# bits.net
KiCad netlist of a schematic drawn in EAGLE
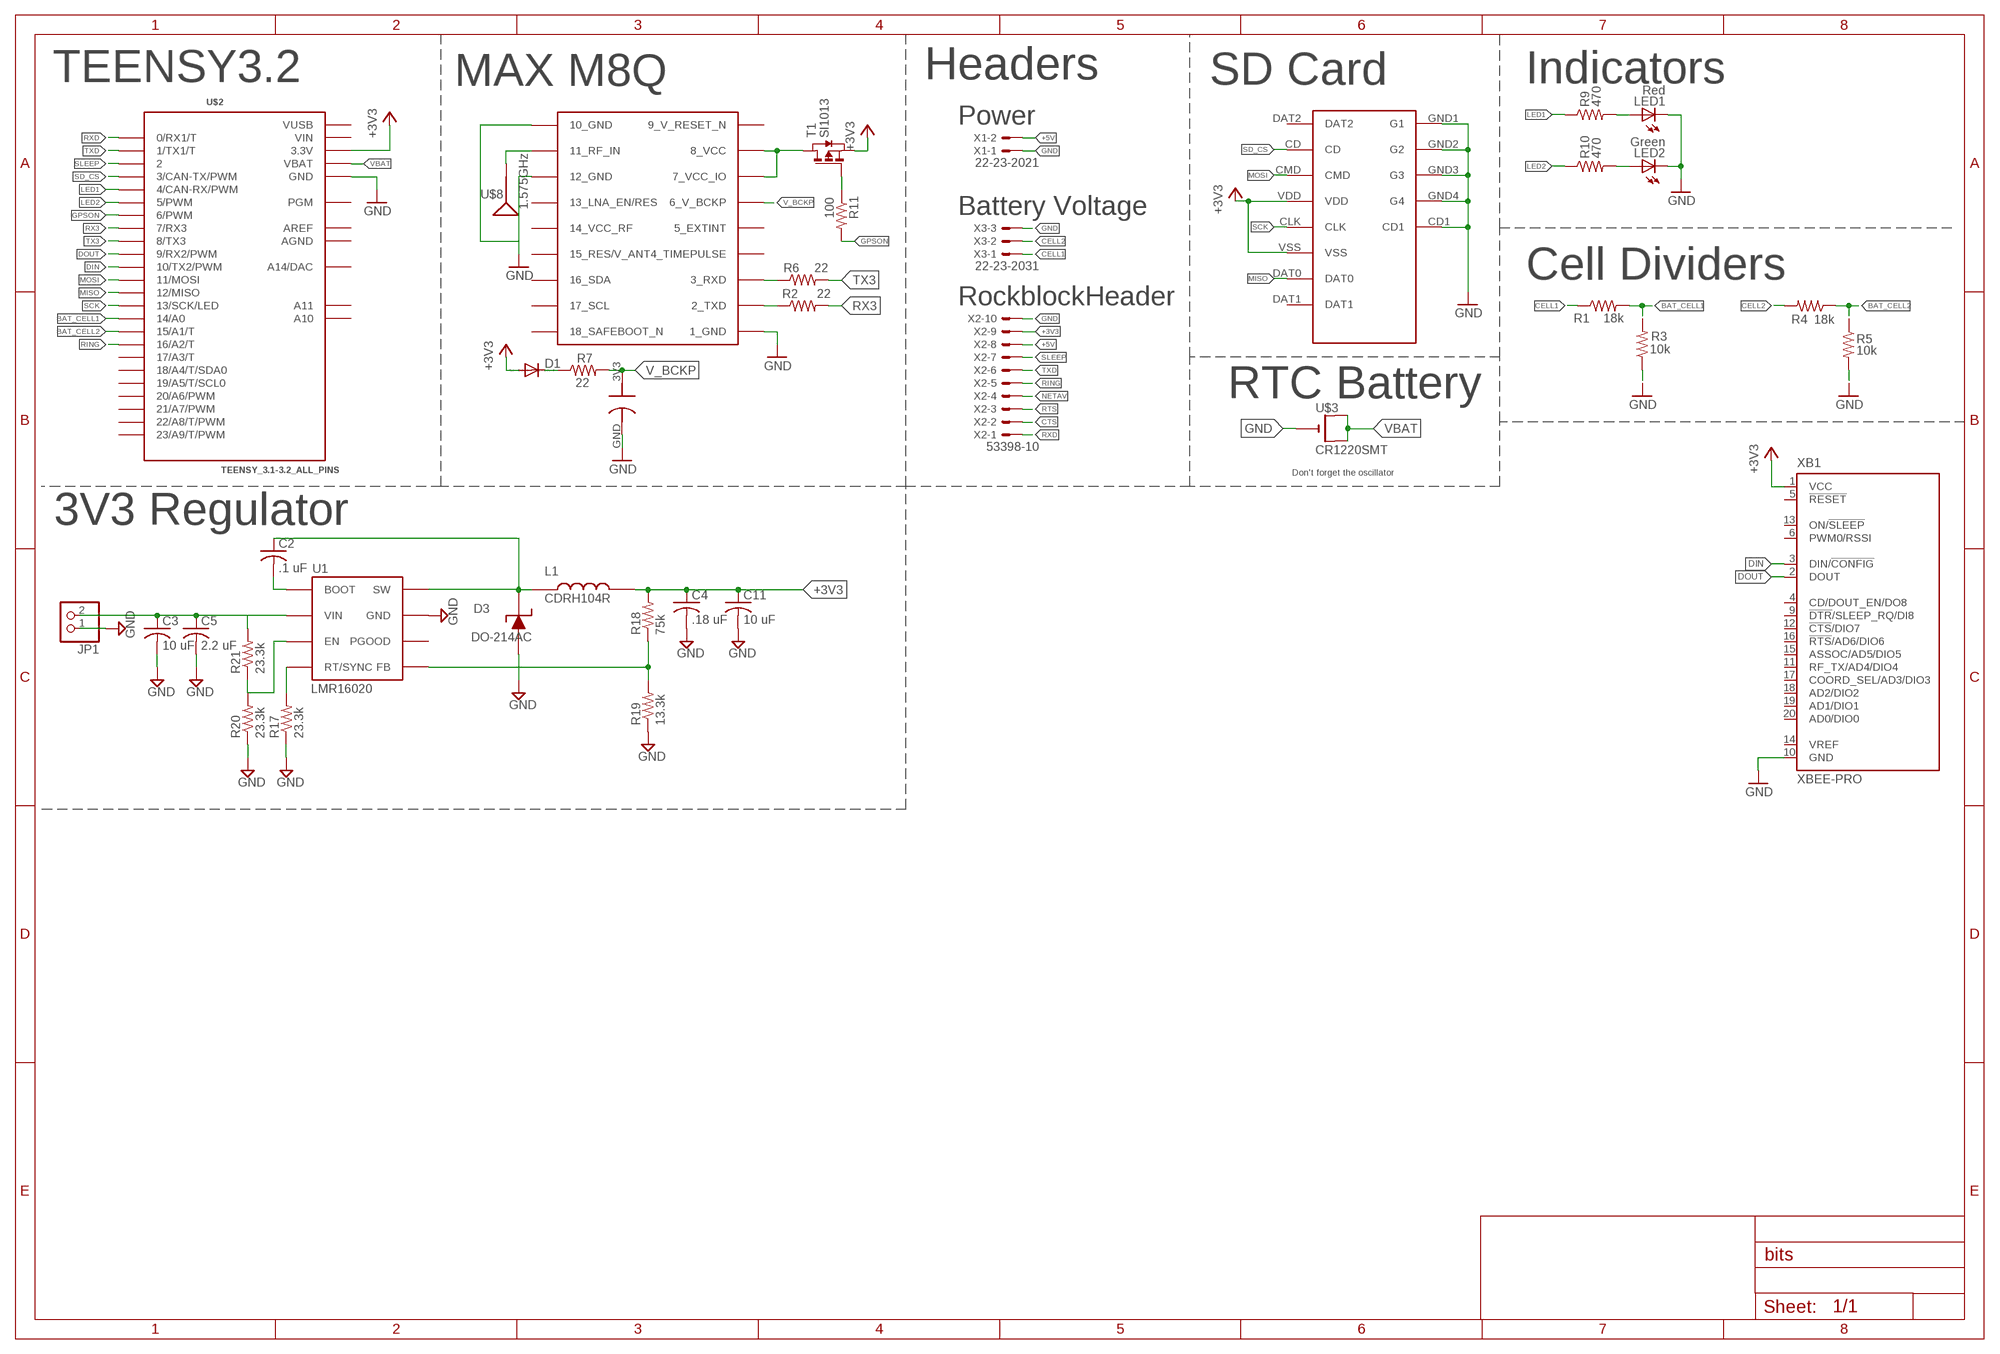
[diagram p0: schematic, sheet 1]

(export (version "E")
  (design (tool "Eeschema 10.0.6"))
  (components
    (comp (ref "C1")
      (value "DCK-3R3E204T614-E")
      (footprint "eagle-import:ELNASUPERCAP")
      (libsource (lib "eagle-import") (part "DCK-3R3E204T614-E"))
    )
    (comp (ref "C2")
      (value ".1 uF")
      (footprint "eagle-import:C0603")
      (libsource (lib "eagle-import") (part "C-USC0603"))
    )
    (comp (ref "C3")
      (value "10 uF")
      (footprint "eagle-import:C1210")
      (libsource (lib "eagle-import") (part "C-USC1210"))
    )
    (comp (ref "C4")
      (value ".18 uF")
      (footprint "eagle-import:C0603")
      (libsource (lib "eagle-import") (part "C-USC0603"))
    )
    (comp (ref "C5")
      (value "2.2 uF")
      (footprint "eagle-import:C1210")
      (libsource (lib "eagle-import") (part "C-USC1210"))
    )
    (comp (ref "C11")
      (value "10 uF")
      (footprint "eagle-import:C0603")
      (libsource (lib "eagle-import") (part "C-USC0603"))
    )
    (comp (ref "D1")
      (value "DIODE-SOD523")
      (footprint "eagle-import:SOD523")
      (libsource (lib "eagle-import") (part "DIODE-SOD523"))
    )
    (comp (ref "D3")
      (value "DO-214AC")
      (footprint "eagle-import:DO-214AC")
      (libsource (lib "eagle-import") (part "DO-214AC"))
    )
    (comp (ref "JP1")
      (value "PINHD-1X2")
      (footprint "eagle-import:1X02")
      (libsource (lib "eagle-import") (part "PINHD-1X2"))
    )
    (comp (ref "L1")
      (value "CDRH104R")
      (footprint "eagle-import:CDRH104R")
      (libsource (lib "eagle-import") (part "CDRH104R"))
    )
    (comp (ref "LED1")
      (value "Red")
      (footprint "eagle-import:CHIP-LED0603")
      (libsource (lib "eagle-import") (part "LEDCHIP-LED0603"))
    )
    (comp (ref "LED2")
      (value "Green")
      (footprint "eagle-import:CHIP-LED0603")
      (libsource (lib "eagle-import") (part "LEDCHIP-LED0603"))
    )
    (comp (ref "R1")
      (value "18k")
      (footprint "eagle-import:R0603")
      (libsource (lib "eagle-import") (part "resistor_R-US_R0603"))
    )
    (comp (ref "R2")
      (value "22")
      (footprint "eagle-import:R0603")
      (libsource (lib "eagle-import") (part "R-US_R0603"))
    )
    (comp (ref "R3")
      (value "10k")
      (footprint "eagle-import:R0603")
      (libsource (lib "eagle-import") (part "resistor_R-US_R0603"))
    )
    (comp (ref "R4")
      (value "18k")
      (footprint "eagle-import:R0603")
      (libsource (lib "eagle-import") (part "resistor_R-US_R0603"))
    )
    (comp (ref "R5")
      (value "10k")
      (footprint "eagle-import:R0603")
      (libsource (lib "eagle-import") (part "resistor_R-US_R0603"))
    )
    (comp (ref "R6")
      (value "22")
      (footprint "eagle-import:R0603")
      (libsource (lib "eagle-import") (part "R-US_R0603"))
    )
    (comp (ref "R7")
      (value "22")
      (footprint "eagle-import:R0603")
      (libsource (lib "eagle-import") (part "R-US_R0603"))
    )
    (comp (ref "R9")
      (value "470")
      (footprint "eagle-import:R0603")
      (libsource (lib "eagle-import") (part "resistor_R-US_R0603"))
    )
    (comp (ref "R10")
      (value "470")
      (footprint "eagle-import:R0603")
      (libsource (lib "eagle-import") (part "resistor_R-US_R0603"))
    )
    (comp (ref "R11")
      (value "100")
      (footprint "eagle-import:R0603")
      (libsource (lib "eagle-import") (part "R-US_R0603"))
    )
    (comp (ref "R17")
      (value "23.3k")
      (footprint "eagle-import:R0603")
      (libsource (lib "eagle-import") (part "resistor_R-US_R0603"))
    )
    (comp (ref "R18")
      (value "75k")
      (footprint "eagle-import:R0603")
      (libsource (lib "eagle-import") (part "resistor_R-US_R0603"))
    )
    (comp (ref "R19")
      (value "13.3k")
      (footprint "eagle-import:R0603")
      (libsource (lib "eagle-import") (part "resistor_R-US_R0603"))
    )
    (comp (ref "R20")
      (value "23.3k")
      (footprint "eagle-import:R0603")
      (libsource (lib "eagle-import") (part "resistor_R-US_R0603"))
    )
    (comp (ref "R21")
      (value "23.3k")
      (footprint "eagle-import:R0603")
      (libsource (lib "eagle-import") (part "resistor_R-US_R0603"))
    )
    (comp (ref "T1")
      (value "SI1013")
      (footprint "eagle-import:SC-75")
      (libsource (lib "eagle-import") (part "SI1013"))
    )
    (comp (ref "U$2")
      (value "TEENSY_3.1-3.2_ALL_PINS")
      (footprint "eagle-import:TEENSY_3.0-3.2&LC_ALL_PINS")
      (libsource (lib "eagle-import") (part "TEENSY_3.1-3.2_ALL_PINS"))
    )
    (comp (ref "U$3")
      (value "CR1220SMT")
      (footprint "eagle-import:CR1220-SMD")
      (libsource (lib "eagle-import") (part "CR1220SMT"))
    )
    (comp (ref "U$4")
      (value "MICRO_SD")
      (footprint "eagle-import:MICRO_SD_HINGED")
      (libsource (lib "eagle-import") (part "MICRO_SD"))
    )
    (comp (ref "U$7")
      (value "MAX-M8")
      (footprint "eagle-import:MAX-M8")
      (libsource (lib "eagle-import") (part "MAX-M8"))
    )
    (comp (ref "U$8")
      (value "1.575GHz")
      (footprint "eagle-import:SPARKFUN-GPS_ANT-GPS-2X7MM")
      (libsource (lib "eagle-import") (part "SPARKFUN-GPS_ANTENNAGPS-2X7MM"))
    )
    (comp (ref "U1")
      (value "LMR16020")
      (footprint "eagle-import:SO8")
      (libsource (lib "eagle-import") (part "LMR16020"))
    )
    (comp (ref "X1")
      (value "22-23-2021")
      (footprint "eagle-import:22-23-2021")
      (fields (field (name "MF") "MOLEX"))
      (libsource (lib "eagle-import") (part "22-23-2021"))
    )
    (comp (ref "X2")
      (value "53398-10")
      (footprint "eagle-import:53398-10")
      (fields (field (name "MF") "MOLEX") (field (name "MPN") "53398-1071"))
      (libsource (lib "eagle-import") (part "53?-10398"))
    )
    (comp (ref "X3")
      (value "22-23-2031")
      (footprint "eagle-import:22-23-2031")
      (fields (field (name "MF") "MOLEX"))
      (libsource (lib "eagle-import") (part "22-23-2031"))
    )
    (comp (ref "XB1")
      (value "XBEE-PRO")
      (footprint "eagle-import:XBEE-PRO")
      (fields (field (name "MPN") "XBP24-AWI-001"))
      (libsource (lib "eagle-import") (part "XBEE-PRO"))
    )
  )
  (nets
    (net (code "1") (name "+3V3") (class "Default")
      (node (ref "C11") (pin "1") (pinfunction "1_1") (pintype "passive"))
      (node (ref "C4") (pin "1") (pinfunction "1_1") (pintype "passive"))
      (node (ref "D1") (pin "A") (pinfunction "A_A") (pintype "passive"))
      (node (ref "L1") (pin "P$2") (pinfunction "P$2_P$2") (pintype "bidirectional"))
      (node (ref "R18") (pin "2") (pinfunction "2_2") (pintype "passive"))
      (node (ref "T1") (pin "P$2") (pinfunction "S_P$2") (pintype "passive"))
      (node (ref "U$2") (pin "3.3V") (pinfunction "3.3V_3.3V") (pintype "power_in"))
      (node (ref "U$2") (pin "3.3V1") (pinfunction "3.3V_3.3V1") (pintype "power_in"))
      (node (ref "U$4") (pin "VDD") (pinfunction "VDD_VDD") (pintype "bidirectional"))
      (node (ref "U$4") (pin "VSS") (pinfunction "VSS_VSS") (pintype "bidirectional"))
      (node (ref "X2") (pin "9") (pinfunction "S_9") (pintype "passive"))
      (node (ref "XB1") (pin "1") (pinfunction "VCC_1") (pintype "power_in"))
    )
    (net (code "2") (name "+5V") (class "Default")
      (node (ref "X1") (pin "2") (pinfunction "S_2") (pintype "passive"))
      (node (ref "X2") (pin "8") (pinfunction "S_8") (pintype "passive"))
    )
    (net (code "3") (name "/9_V_RESET_N") (class "Default")
      (node (ref "U$7") (pin "9_RESET_N") (pinfunction "9_V_RESET_N_9_RESET_N") (pintype "power_in"))
    )
    (net (code "4") (name "/AGND") (class "Default")
      (node (ref "U$2") (pin "AGND") (pinfunction "AGND_AGND") (pintype "power_in"))
    )
    (net (code "5") (name "/AREF") (class "Default")
      (node (ref "U$2") (pin "AREF") (pinfunction "AREF_AREF") (pintype "power_in"))
    )
    (net (code "6") (name "/VIN") (class "Default")
      (node (ref "U$2") (pin "VIN") (pinfunction "VIN_VIN") (pintype "power_in"))
    )
    (net (code "7") (name "/VUSB") (class "Default")
      (node (ref "U$2") (pin "VUSB") (pinfunction "VUSB_VUSB") (pintype "power_in"))
    )
    (net (code "8") (name "BAT_CELL1") (class "Default")
      (node (ref "R1") (pin "2") (pinfunction "2_2") (pintype "passive"))
      (node (ref "R3") (pin "2") (pinfunction "2_2") (pintype "passive"))
      (node (ref "U$2") (pin "14/A0") (pinfunction "14/A0_14/A0") (pintype "bidirectional"))
    )
    (net (code "9") (name "BAT_CELL2") (class "Default")
      (node (ref "R4") (pin "1") (pinfunction "1_1") (pintype "passive"))
      (node (ref "R5") (pin "1") (pinfunction "1_1") (pintype "passive"))
      (node (ref "U$2") (pin "15/A1") (pinfunction "15/A1/T_15/A1") (pintype "bidirectional"))
    )
    (net (code "10") (name "CELL1") (class "Default")
      (node (ref "R1") (pin "1") (pinfunction "1_1") (pintype "passive"))
      (node (ref "X3") (pin "1") (pinfunction "S_1") (pintype "passive"))
    )
    (net (code "11") (name "CELL2") (class "Default")
      (node (ref "R4") (pin "2") (pinfunction "2_2") (pintype "passive"))
      (node (ref "X3") (pin "2") (pinfunction "S_2") (pintype "passive"))
    )
    (net (code "12") (name "CTS") (class "Default")
      (node (ref "X2") (pin "2") (pinfunction "S_2") (pintype "passive"))
    )
    (net (code "13") (name "DIN") (class "Default")
      (node (ref "U$2") (pin "10") (pinfunction "10/TX2/PWM_10") (pintype "bidirectional"))
      (node (ref "XB1") (pin "3") (pinfunction "DIN/~{CONFIG}_3") (pintype "input"))
    )
    (net (code "14") (name "DOUT") (class "Default")
      (node (ref "U$2") (pin "9") (pinfunction "9/RX2/PWM_9") (pintype "bidirectional"))
      (node (ref "XB1") (pin "2") (pinfunction "DOUT_2") (pintype "output"))
    )
    (net (code "15") (name "GND") (class "Default")
      (node (ref "C1") (pin "GND") (pinfunction "GND_GND") (pintype "bidirectional"))
      (node (ref "C11") (pin "2") (pinfunction "2_2") (pintype "passive"))
      (node (ref "C3") (pin "2") (pinfunction "2_2") (pintype "passive"))
      (node (ref "C4") (pin "2") (pinfunction "2_2") (pintype "passive"))
      (node (ref "C5") (pin "2") (pinfunction "2_2") (pintype "passive"))
      (node (ref "D3") (pin "P$1") (pinfunction "P$1_P$1") (pintype "bidirectional"))
      (node (ref "JP1") (pin "1") (pinfunction "1_1") (pintype "passive"))
      (node (ref "LED1") (pin "C") (pinfunction "C_C") (pintype "passive"))
      (node (ref "LED2") (pin "C") (pinfunction "C_C") (pintype "passive"))
      (node (ref "R17") (pin "1") (pinfunction "1_1") (pintype "passive"))
      (node (ref "R19") (pin "1") (pinfunction "1_1") (pintype "passive"))
      (node (ref "R20") (pin "1") (pinfunction "1_1") (pintype "passive"))
      (node (ref "R3") (pin "1") (pinfunction "1_1") (pintype "passive"))
      (node (ref "R5") (pin "2") (pinfunction "2_2") (pintype "passive"))
      (node (ref "U$2") (pin "GND") (pinfunction "GND_GND") (pintype "power_in"))
      (node (ref "U$2") (pin "GND1") (pinfunction "GND_GND1") (pintype "power_in"))
      (node (ref "U$3") (pin "-") (pinfunction "-_-") (pintype "passive"))
      (node (ref "U$4") (pin "CD1") (pinfunction "CD1_CD1") (pintype "bidirectional"))
      (node (ref "U$4") (pin "GND1") (pinfunction "G1_GND1") (pintype "bidirectional"))
      (node (ref "U$4") (pin "GND2") (pinfunction "G2_GND2") (pintype "bidirectional"))
      (node (ref "U$4") (pin "GND3") (pinfunction "G3_GND3") (pintype "bidirectional"))
      (node (ref "U$4") (pin "GND4") (pinfunction "G4_GND4") (pintype "bidirectional"))
      (node (ref "U$7") (pin "10_GND") (pinfunction "10_GND_10_GND") (pintype "power_in"))
      (node (ref "U$7") (pin "12_GND") (pinfunction "12_GND_12_GND") (pintype "power_in"))
      (node (ref "U$7") (pin "1_GND") (pinfunction "1_GND_1_GND") (pintype "power_in"))
      (node (ref "U1") (pin "P$7") (pinfunction "GND_P$7") (pintype "bidirectional"))
      (node (ref "U1") (pin "PAD") (pinfunction "GND_PAD") (pintype "bidirectional"))
      (node (ref "X1") (pin "1") (pinfunction "S_1") (pintype "passive"))
      (node (ref "X2") (pin "10") (pinfunction "S_10") (pintype "passive"))
      (node (ref "X3") (pin "3") (pinfunction "S_3") (pintype "passive"))
      (node (ref "XB1") (pin "10") (pinfunction "GND_10") (pintype "power_in"))
    )
    (net (code "16") (name "GPSON") (class "Default")
      (node (ref "R11") (pin "2") (pinfunction "2_2") (pintype "passive"))
      (node (ref "U$2") (pin "6") (pinfunction "6/PWM_6") (pintype "bidirectional"))
    )
    (net (code "17") (name "LED1") (class "Default")
      (node (ref "R9") (pin "1") (pinfunction "1_1") (pintype "passive"))
      (node (ref "U$2") (pin "4") (pinfunction "4/CAN-RX/PWM_4") (pintype "bidirectional"))
    )
    (net (code "18") (name "LED2") (class "Default")
      (node (ref "R10") (pin "1") (pinfunction "1_1") (pintype "passive"))
      (node (ref "U$2") (pin "5") (pinfunction "5/PWM_5") (pintype "bidirectional"))
    )
    (net (code "19") (name "MISO") (class "Default")
      (node (ref "U$2") (pin "12") (pinfunction "12/MISO_12") (pintype "bidirectional"))
      (node (ref "U$4") (pin "DAT0") (pinfunction "DAT0_DAT0") (pintype "bidirectional"))
    )
    (net (code "20") (name "MOSI") (class "Default")
      (node (ref "U$2") (pin "11") (pinfunction "11/MOSI_11") (pintype "bidirectional"))
      (node (ref "U$4") (pin "CMD") (pinfunction "CMD_CMD") (pintype "bidirectional"))
    )
    (net (code "21") (name "NETAV") (class "Default")
      (node (ref "X2") (pin "4") (pinfunction "S_4") (pintype "passive"))
    )
    (net (code "22") (name "Net-(D1-PadC)") (class "Default")
      (node (ref "D1") (pin "C") (pinfunction "C_C") (pintype "passive"))
      (node (ref "R7") (pin "1") (pinfunction "1_1") (pintype "passive"))
    )
    (net (code "23") (name "Net-(LED1-PadA)") (class "Default")
      (node (ref "LED1") (pin "A") (pinfunction "A_A") (pintype "passive"))
      (node (ref "R9") (pin "2") (pinfunction "2_2") (pintype "passive"))
    )
    (net (code "24") (name "Net-(LED2-PadA)") (class "Default")
      (node (ref "LED2") (pin "A") (pinfunction "A_A") (pintype "passive"))
      (node (ref "R10") (pin "2") (pinfunction "2_2") (pintype "passive"))
    )
    (net (code "25") (name "Net-(R2-Pad1)") (class "Default")
      (node (ref "R2") (pin "1") (pinfunction "1_1") (pintype "passive"))
      (node (ref "U$7") (pin "2_TXD") (pinfunction "2_TXD_2_TXD") (pintype "bidirectional"))
    )
    (net (code "26") (name "Net-(R6-Pad1)") (class "Default")
      (node (ref "R6") (pin "1") (pinfunction "1_1") (pintype "passive"))
      (node (ref "U$7") (pin "3_RXD") (pinfunction "3_RXD_3_RXD") (pintype "bidirectional"))
    )
    (net (code "27") (name "Net-(T1-D)") (class "Default")
      (node (ref "T1") (pin "P$3") (pinfunction "D_P$3") (pintype "passive"))
      (node (ref "U$7") (pin "7_VCC_IO") (pinfunction "7_VCC_IO_7_VCC_IO") (pintype "power_in"))
      (node (ref "U$7") (pin "8_VCC") (pinfunction "8_VCC_8_VCC") (pintype "power_in"))
    )
    (net (code "28") (name "Net-(T1-G)") (class "Default")
      (node (ref "R11") (pin "1") (pinfunction "1_1") (pintype "passive"))
      (node (ref "T1") (pin "P$1") (pinfunction "G_P$1") (pintype "passive"))
    )
    (net (code "29") (name "Net-(U$8-SIGNAL)") (class "Default")
      (node (ref "U$7") (pin "11_RF_IN") (pinfunction "11_RF_IN_11_RF_IN") (pintype "bidirectional"))
      (node (ref "U$8") (pin "1") (pinfunction "SIGNAL_1") (pintype "bidirectional"))
    )
    (net (code "30") (name "Net-(U1-BOOT)") (class "Default")
      (node (ref "C2") (pin "2") (pinfunction "2_2") (pintype "passive"))
      (node (ref "U1") (pin "P$1") (pinfunction "BOOT_P$1") (pintype "bidirectional"))
    )
    (net (code "31") (name "Net-(U1-EN)") (class "Default")
      (node (ref "R20") (pin "2") (pinfunction "2_2") (pintype "passive"))
      (node (ref "R21") (pin "1") (pinfunction "1_1") (pintype "passive"))
      (node (ref "U1") (pin "P$3") (pinfunction "EN_P$3") (pintype "bidirectional"))
    )
    (net (code "32") (name "Net-(U1-FB)") (class "Default")
      (node (ref "R18") (pin "1") (pinfunction "1_1") (pintype "passive"))
      (node (ref "R19") (pin "2") (pinfunction "2_2") (pintype "passive"))
      (node (ref "U1") (pin "P$5") (pinfunction "FB_P$5") (pintype "bidirectional"))
    )
    (net (code "33") (name "Net-(U1-RT{slash}SYNC)") (class "Default")
      (node (ref "R17") (pin "2") (pinfunction "2_2") (pintype "passive"))
      (node (ref "U1") (pin "P$4") (pinfunction "RT/SYNC_P$4") (pintype "bidirectional"))
    )
    (net (code "34") (name "Net-(U1-SW)") (class "Default")
      (node (ref "C2") (pin "1") (pinfunction "1_1") (pintype "passive"))
      (node (ref "D3") (pin "P$2") (pinfunction "P$2_P$2") (pintype "bidirectional"))
      (node (ref "L1") (pin "P$1") (pinfunction "P$1_P$1") (pintype "bidirectional"))
      (node (ref "U1") (pin "P$8") (pinfunction "SW_P$8") (pintype "bidirectional"))
    )
    (net (code "35") (name "Net-(U1-VIN)") (class "Default")
      (node (ref "C3") (pin "1") (pinfunction "1_1") (pintype "passive"))
      (node (ref "C5") (pin "1") (pinfunction "1_1") (pintype "passive"))
      (node (ref "JP1") (pin "2") (pinfunction "2_2") (pintype "passive"))
      (node (ref "R21") (pin "2") (pinfunction "2_2") (pintype "passive"))
      (node (ref "U1") (pin "P$2") (pinfunction "VIN_P$2") (pintype "bidirectional"))
    )
    (net (code "36") (name "RING") (class "Default")
      (node (ref "U$2") (pin "16/A2") (pinfunction "16/A2/T_16/A2") (pintype "bidirectional"))
      (node (ref "X2") (pin "5") (pinfunction "S_5") (pintype "passive"))
    )
    (net (code "37") (name "RTS") (class "Default")
      (node (ref "X2") (pin "3") (pinfunction "S_3") (pintype "passive"))
    )
    (net (code "38") (name "RX3") (class "Default")
      (node (ref "R2") (pin "2") (pinfunction "2_2") (pintype "passive"))
      (node (ref "U$2") (pin "7") (pinfunction "7/RX3_7") (pintype "bidirectional"))
    )
    (net (code "39") (name "RXD") (class "Default")
      (node (ref "U$2") (pin "0") (pinfunction "0/RX1/T_0") (pintype "bidirectional"))
      (node (ref "X2") (pin "1") (pinfunction "S_1") (pintype "passive"))
    )
    (net (code "40") (name "SCK") (class "Default")
      (node (ref "U$2") (pin "13") (pinfunction "13/SCK/LED_13") (pintype "bidirectional"))
      (node (ref "U$4") (pin "CLK") (pinfunction "CLK_CLK") (pintype "bidirectional"))
    )
    (net (code "41") (name "SD_CS") (class "Default")
      (node (ref "U$2") (pin "3") (pinfunction "3/CAN-TX/PWM_3") (pintype "bidirectional"))
      (node (ref "U$4") (pin "CD") (pinfunction "CD_CD") (pintype "bidirectional"))
    )
    (net (code "42") (name "SLEEP") (class "Default")
      (node (ref "U$2") (pin "2") (pinfunction "2_2") (pintype "bidirectional"))
      (node (ref "X2") (pin "7") (pinfunction "S_7") (pintype "passive"))
    )
    (net (code "43") (name "TX3") (class "Default")
      (node (ref "R6") (pin "2") (pinfunction "2_2") (pintype "passive"))
      (node (ref "U$2") (pin "8") (pinfunction "8/TX3_8") (pintype "bidirectional"))
    )
    (net (code "44") (name "TXD") (class "Default")
      (node (ref "U$2") (pin "1") (pinfunction "1/TX1/T_1") (pintype "bidirectional"))
      (node (ref "X2") (pin "6") (pinfunction "S_6") (pintype "passive"))
    )
    (net (code "45") (name "VBAT") (class "Default")
      (node (ref "U$2") (pin "VBAT") (pinfunction "VBAT_VBAT") (pintype "power_in"))
      (node (ref "U$3") (pin "+$1") (pinfunction "+_+$1") (pintype "passive"))
      (node (ref "U$3") (pin "+$2") (pinfunction "+1_+$2") (pintype "passive"))
    )
    (net (code "46") (name "V_BCKP") (class "Default")
      (node (ref "C1") (pin "3V3") (pinfunction "3V3_3V3") (pintype "bidirectional"))
      (node (ref "R7") (pin "2") (pinfunction "2_2") (pintype "passive"))
      (node (ref "U$7") (pin "6_V_BCKP") (pinfunction "6_V_BCKP_6_V_BCKP") (pintype "bidirectional"))
    )
    (net (code "47") (name "unconnected-(U$2-17{slash}A3{slash}T-Pad17{slash}A3)") (class "Default")
      (node (ref "U$2") (pin "17/A3") (pinfunction "17/A3/T_17/A3") (pintype "bidirectional"))
    )
    (net (code "48") (name "unconnected-(U$2-18{slash}A4{slash}T{slash}SDA0-Pad18{slash}A4)") (class "Default")
      (node (ref "U$2") (pin "18/A4") (pinfunction "18/A4/T/SDA0_18/A4") (pintype "bidirectional"))
    )
    (net (code "49") (name "unconnected-(U$2-19{slash}A5{slash}T{slash}SCL0-Pad19{slash}A5)") (class "Default")
      (node (ref "U$2") (pin "19/A5") (pinfunction "19/A5/T/SCL0_19/A5") (pintype "bidirectional"))
    )
    (net (code "50") (name "unconnected-(U$2-20{slash}A6{slash}PWM-Pad20{slash}A6)") (class "Default")
      (node (ref "U$2") (pin "20/A6") (pinfunction "20/A6/PWM_20/A6") (pintype "bidirectional"))
    )
    (net (code "51") (name "unconnected-(U$2-21{slash}A7{slash}PWM-Pad21{slash}A7)") (class "Default")
      (node (ref "U$2") (pin "21/A7") (pinfunction "21/A7/PWM_21/A7") (pintype "bidirectional"))
    )
    (net (code "52") (name "unconnected-(U$2-22{slash}A8{slash}T{slash}PWM-Pad22{slash}A8)") (class "Default")
      (node (ref "U$2") (pin "22/A8") (pinfunction "22/A8/T/PWM_22/A8") (pintype "bidirectional"))
    )
    (net (code "53") (name "unconnected-(U$2-23{slash}A9{slash}T{slash}PWM-Pad23{slash}A9)") (class "Default")
      (node (ref "U$2") (pin "23/A9") (pinfunction "23/A9/T/PWM_23/A9") (pintype "bidirectional"))
    )
    (net (code "54") (name "unconnected-(U$2-A14{slash}DAC-PadRESET{slash}DAC)") (class "Default")
      (node (ref "U$2") (pin "RESET/DAC") (pinfunction "A14/DAC_RESET/DAC") (pintype "bidirectional"))
    )
    (net (code "55") (name "unconnected-(U$2-PadA10)") (class "Default")
      (node (ref "U$2") (pin "A10") (pinfunction "A10_A10") (pintype "bidirectional"))
    )
    (net (code "56") (name "unconnected-(U$2-PadA11)") (class "Default")
      (node (ref "U$2") (pin "A11") (pinfunction "A11_A11") (pintype "bidirectional"))
    )
    (net (code "57") (name "unconnected-(U$2-PadPGM)") (class "Default")
      (node (ref "U$2") (pin "PGM") (pinfunction "PGM_PGM") (pintype "bidirectional"))
    )
    (net (code "58") (name "unconnected-(U$4-PadDAT1)") (class "Default")
      (node (ref "U$4") (pin "DAT1") (pinfunction "DAT1_DAT1") (pintype "bidirectional"))
    )
    (net (code "59") (name "unconnected-(U$4-PadDAT2)") (class "Default")
      (node (ref "U$4") (pin "DAT2") (pinfunction "DAT2_DAT2") (pintype "bidirectional"))
    )
    (net (code "60") (name "unconnected-(U$7-13_LNA_EN{slash}RES-Pad13_LNA_EN)") (class "Default")
      (node (ref "U$7") (pin "13_LNA_EN") (pinfunction "13_LNA_EN/RES_13_LNA_EN") (pintype "bidirectional"))
    )
    (net (code "61") (name "unconnected-(U$7-15_RES{slash}V_ANT-Pad15_V_ANT{slash}RESERVED)") (class "Default")
      (node (ref "U$7") (pin "15_V_ANT/RESERVED") (pinfunction "15_RES/V_ANT_15_V_ANT/RESERVED") (pintype "bidirectional"))
    )
    (net (code "62") (name "unconnected-(U$7-Pad4_TIMEPULSE)") (class "Default")
      (node (ref "U$7") (pin "4_TIMEPULSE") (pinfunction "4_TIMEPULSE_4_TIMEPULSE") (pintype "bidirectional"))
    )
    (net (code "63") (name "unconnected-(U$7-Pad5_EXTINT)") (class "Default")
      (node (ref "U$7") (pin "5_EXTINT") (pinfunction "5_EXTINT_5_EXTINT") (pintype "bidirectional"))
    )
    (net (code "64") (name "unconnected-(U$7-Pad14_VCC_RF)") (class "Default")
      (node (ref "U$7") (pin "14_VCC_RF") (pinfunction "14_VCC_RF_14_VCC_RF") (pintype "bidirectional"))
    )
    (net (code "65") (name "unconnected-(U$7-Pad16_SDA)") (class "Default")
      (node (ref "U$7") (pin "16_SDA") (pinfunction "16_SDA_16_SDA") (pintype "bidirectional"))
    )
    (net (code "66") (name "unconnected-(U$7-Pad17_SCL)") (class "Default")
      (node (ref "U$7") (pin "17_SCL") (pinfunction "17_SCL_17_SCL") (pintype "bidirectional"))
    )
    (net (code "67") (name "unconnected-(U$7-Pad18_SAFEBOOT_N)") (class "Default")
      (node (ref "U$7") (pin "18_SAFEBOOT_N") (pinfunction "18_SAFEBOOT_N_18_SAFEBOOT_N") (pintype "bidirectional"))
    )
    (net (code "68") (name "unconnected-(U1-PGOOD-PadP$6)") (class "Default")
      (node (ref "U1") (pin "P$6") (pinfunction "PGOOD_P$6") (pintype "bidirectional"))
    )
    (net (code "69") (name "unconnected-(XB1-AD0{slash}DIO0-Pad20)") (class "Default")
      (node (ref "XB1") (pin "20") (pinfunction "AD0/DIO0_20") (pintype "bidirectional"))
    )
    (net (code "70") (name "unconnected-(XB1-AD1{slash}DIO1-Pad19)") (class "Default")
      (node (ref "XB1") (pin "19") (pinfunction "AD1/DIO1_19") (pintype "bidirectional"))
    )
    (net (code "71") (name "unconnected-(XB1-AD2{slash}DIO2-Pad18)") (class "Default")
      (node (ref "XB1") (pin "18") (pinfunction "AD2/DIO2_18") (pintype "bidirectional"))
    )
    (net (code "72") (name "unconnected-(XB1-ASSOC{slash}AD5{slash}DIO5-Pad15)") (class "Default")
      (node (ref "XB1") (pin "15") (pinfunction "ASSOC/AD5/DIO5_15") (pintype "bidirectional"))
    )
    (net (code "73") (name "unconnected-(XB1-CD{slash}DOUT_EN{slash}DO8-Pad4)") (class "Default")
      (node (ref "XB1") (pin "4") (pinfunction "CD/DOUT_EN/DO8_4") (pintype "output"))
    )
    (net (code "74") (name "unconnected-(XB1-COORD_SEL{slash}AD3{slash}DIO3-Pad17)") (class "Default")
      (node (ref "XB1") (pin "17") (pinfunction "COORD_SEL/AD3/DIO3_17") (pintype "bidirectional"))
    )
    (net (code "75") (name "unconnected-(XB1-ON{slash}~{SLEEP}-Pad13)") (class "Default")
      (node (ref "XB1") (pin "13") (pinfunction "ON/~{SLEEP}_13") (pintype "output"))
    )
    (net (code "76") (name "unconnected-(XB1-PWM0{slash}RSSI-Pad6)") (class "Default")
      (node (ref "XB1") (pin "6") (pinfunction "PWM0/RSSI_6") (pintype "output"))
    )
    (net (code "77") (name "unconnected-(XB1-RF_TX{slash}AD4{slash}DIO4-Pad11)") (class "Default")
      (node (ref "XB1") (pin "11") (pinfunction "RF_TX/AD4/DIO4_11") (pintype "bidirectional"))
    )
    (net (code "78") (name "unconnected-(XB1-VREF-Pad14)") (class "Default")
      (node (ref "XB1") (pin "14") (pinfunction "VREF_14") (pintype "input"))
    )
    (net (code "79") (name "unconnected-(XB1-~{CTS}{slash}DIO7-Pad12)") (class "Default")
      (node (ref "XB1") (pin "12") (pinfunction "~{CTS}/DIO7_12") (pintype "bidirectional"))
    )
    (net (code "80") (name "unconnected-(XB1-~{DTR}{slash}SLEEP_RQ{slash}DI8-Pad9)") (class "Default")
      (node (ref "XB1") (pin "9") (pinfunction "~{DTR}/SLEEP_RQ/DI8_9") (pintype "bidirectional"))
    )
    (net (code "81") (name "unconnected-(XB1-~{RESET}-Pad5)") (class "Default")
      (node (ref "XB1") (pin "5") (pinfunction "~{RESET}_5") (pintype "input"))
    )
    (net (code "82") (name "unconnected-(XB1-~{RTS}{slash}AD6{slash}DIO6-Pad16)") (class "Default")
      (node (ref "XB1") (pin "16") (pinfunction "~{RTS}/AD6/DIO6_16") (pintype "bidirectional"))
    )
  )
)
